# hx711.net
KiCad netlist of a schematic drawn in Altium Designer
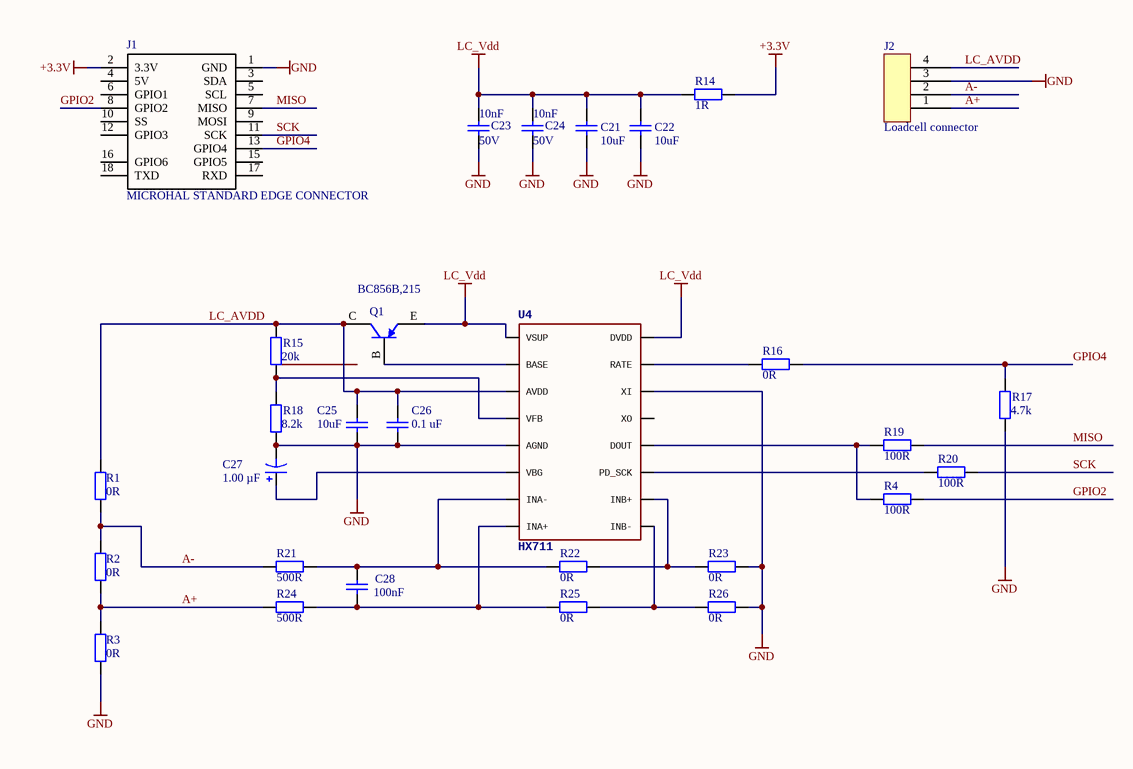
[diagram p0: hx711.SchDoc]

(export (version "E")
  (design (tool "Eeschema 10.0.6"))
  (components
    (comp (ref "C21")
      (value "AVX Interconnect / Elco TAJR106K006RNJ")
      (footprint "CAPC2113X120X50LL20T30")
      (description "CAP TANT 10UF 6.3V 10% 0805")
      (fields
        (field (name "VOLTAGE") "6.3VDC")
        (field (name "MANUFACTURER PART NUMBER") "TAJR106K006RNJ")
        (field (name "CAPACITANCE") "10uF")
      )
      (libsource (lib "CommunityVault") (part "CAP-2"))
    )
    (comp (ref "C22")
      (value "AVX Interconnect / Elco TAJR106K006RNJ")
      (footprint "CAPC2113X120X50LL20T30")
      (description "CAP TANT 10UF 6.3V 10% 0805")
      (fields
        (field (name "VOLTAGE") "6.3VDC")
        (field (name "MANUFACTURER PART NUMBER") "TAJR106K006RNJ")
        (field (name "CAPACITANCE") "10uF")
      )
      (libsource (lib "CommunityVault") (part "CAP-2"))
    )
    (comp (ref "C23")
      (value "0603N103J500")
      (footprint "PCB-19299713-1")
      (fields (field (name "CAPACITANCE") "10nF") (field (name "VOLTAGE RATING (DC)") "50V"))
      (libsource (lib "CommunityVault") (part "CMP-19299713-2"))
    )
    (comp (ref "C24")
      (value "0603N103J500")
      (footprint "PCB-19299713-1")
      (fields (field (name "CAPACITANCE") "10nF") (field (name "VOLTAGE RATING (DC)") "50V"))
      (libsource (lib "CommunityVault") (part "CMP-19299713-2"))
    )
    (comp (ref "C25")
      (value "AVX Interconnect / Elco TAJR106K006RNJ")
      (footprint "CAPC2113X120X50LL20T30")
      (description "CAP TANT 10UF 6.3V 10% 0805")
      (fields
        (field (name "VOLTAGE") "6.3VDC")
        (field (name "MANUFACTURER PART NUMBER") "TAJR106K006RNJ")
        (field (name "CAPACITANCE") "10uF")
      )
      (libsource (lib "CommunityVault") (part "CAP-2"))
    )
    (comp (ref "C26")
      (value "Murata GRM31C5C1E104JA01L")
      (footprint "PCB-121845-2")
      (description "CAP CER 0.1UF 25V 5% NP0 1206")
      (fields
        (field (name "TOLERANCE") "5 %")
        (field (name "MANUFACTURER") "Murata")
        (field (name "CAPACITANCE") "0.1 uF")
      )
      (libsource (lib "CommunityVault") (part "CMP-121845-1"))
    )
    (comp (ref "C27")
      (value "Kemet T491A105M016AT")
      (footprint "CAPC3216X180X80NL20T30")
      (description "Cap Tant Solid 1uF 16V A CASE 20% (3.2 X 1.6 X 1.6mm) SMD 3216-18 10 Ohm 125C Automotive T/R")
      (fields
        (field (name "MANUFACTURER PART NUMBER") "T491A105M016AT")
        (field (name "CAPACITANCE") "1.00 µF")
      )
      (libsource (lib "CommunityVault") (part "CMP-52579b5e2d498d90-1"))
    )
    (comp (ref "C28")
      (value "100nF")
      (footprint "PCB-121845-2")
      (description "CAP CER 0.1UF 25V 5% NP0 1206")
      (libsource (lib "CommunityVault") (part "CMP-121845-2"))
    )
    (comp (ref "J1")
      (value "MICROHAL STANDARD EDGE CONNECTOR")
      (footprint "PCB-n61ghpg3sznbl2uw6fwj-1")
      (description "microhal standard edge connector with 17 pins")
      (libsource (lib "CommunityVault") (part "CMP-6a3uyflm72uf0am1b36s-2"))
    )
    (comp (ref "J2")
      (value "Loadcell connector")
      (footprint "PCBComponent_1")
      (description "Wire-To-Board Connector, AMPMODU Mod II Series, Through Hole, Header, 4, 2.54 mm")
      (fields (field (name "MANUFACTURER PART NUMBER") "826926-4"))
      (libsource (lib "CommunityVault") (part "CMP-5c1097d27ab083d7-2"))
    )
    (comp (ref "Q1")
      (value "BC856B,215")
      (footprint "SOT23-BEC")
      (description "TRANS PNP 65V 0.1A SOT23")
      (libsource (lib "CommunityVault") (part "NXP-PNP-3"))
    )
    (comp (ref "R1")
      (value "~")
      (footprint "0603")
      (fields (field (name "RESISTANCE") "0R"))
      (libsource (lib "") (part "CMP-8f45450282185082-2_1"))
    )
    (comp (ref "R2")
      (value "~")
      (footprint "0603")
      (fields (field (name "RESISTANCE") "0R"))
      (libsource (lib "") (part "CMP-8f45450282185082-2_1"))
    )
    (comp (ref "R3")
      (value "~")
      (footprint "0603")
      (fields (field (name "RESISTANCE") "0R"))
      (libsource (lib "") (part "CMP-8f45450282185082-2_1"))
    )
    (comp (ref "R4")
      (value "~")
      (footprint "0603")
      (fields (field (name "RESISTANCE") "100R"))
      (libsource (lib "CommunityVault") (part "CMP-8f45450282185082-2"))
    )
    (comp (ref "R14")
      (value "~")
      (footprint "0603")
      (fields (field (name "RESISTANCE") "1R"))
      (libsource (lib "CommunityVault") (part "CMP-8f45450282185082-2"))
    )
    (comp (ref "R15")
      (value "~")
      (footprint "0603")
      (fields (field (name "RESISTANCE") "20k"))
      (libsource (lib "") (part "CMP-8f45450282185082-2_2"))
    )
    (comp (ref "R16")
      (value "~")
      (footprint "0603")
      (fields (field (name "RESISTANCE") "0R"))
      (libsource (lib "CommunityVault") (part "CMP-8f45450282185082-2"))
    )
    (comp (ref "R17")
      (value "~")
      (footprint "0603")
      (fields (field (name "RESISTANCE") "4.7k"))
      (libsource (lib "") (part "CMP-8f45450282185082-2_2"))
    )
    (comp (ref "R18")
      (value "~")
      (footprint "0603")
      (fields (field (name "RESISTANCE") "8.2k"))
      (libsource (lib "") (part "CMP-8f45450282185082-2_2"))
    )
    (comp (ref "R19")
      (value "~")
      (footprint "0603")
      (fields (field (name "RESISTANCE") "100R"))
      (libsource (lib "CommunityVault") (part "CMP-8f45450282185082-2"))
    )
    (comp (ref "R20")
      (value "~")
      (footprint "0603")
      (fields (field (name "RESISTANCE") "100R"))
      (libsource (lib "CommunityVault") (part "CMP-8f45450282185082-2"))
    )
    (comp (ref "R21")
      (value "~")
      (footprint "0603")
      (fields (field (name "RESISTANCE") "500R"))
      (libsource (lib "CommunityVault") (part "CMP-8f45450282185082-2"))
    )
    (comp (ref "R22")
      (value "~")
      (footprint "0603")
      (fields (field (name "RESISTANCE") "0R"))
      (libsource (lib "CommunityVault") (part "CMP-8f45450282185082-2"))
    )
    (comp (ref "R23")
      (value "~")
      (footprint "0603")
      (fields (field (name "RESISTANCE") "0R"))
      (libsource (lib "CommunityVault") (part "CMP-8f45450282185082-2"))
    )
    (comp (ref "R24")
      (value "~")
      (footprint "0603")
      (fields (field (name "RESISTANCE") "500R"))
      (libsource (lib "CommunityVault") (part "CMP-8f45450282185082-2"))
    )
    (comp (ref "R25")
      (value "~")
      (footprint "0603")
      (fields (field (name "RESISTANCE") "0R"))
      (libsource (lib "CommunityVault") (part "CMP-8f45450282185082-2"))
    )
    (comp (ref "R26")
      (value "~")
      (footprint "0603")
      (fields (field (name "RESISTANCE") "0R"))
      (libsource (lib "CommunityVault") (part "CMP-8f45450282185082-2"))
    )
    (comp (ref "U4")
      (value "HX711")
      (footprint "CYP-SX16_L")
      (description "Load Cell Amp HX711")
      (libsource (lib "CommunityVault") (part "SYM-8eb44445be3e5173-2"))
    )
  )
  (nets
    (net (code "1") (name "+3.3V") (class "Default")
      (node (ref "J1") (pin "2") (pinfunction "3.3V_2") (pintype "passive"))
      (node (ref "R14") (pin "1") (pinfunction "1_1") (pintype "passive"))
    )
    (net (code "2") (name "/A+") (class "Default")
      (node (ref "J2") (pin "1") (pinfunction "1_1") (pintype "passive"))
      (node (ref "R2") (pin "2") (pinfunction "2_2") (pintype "passive"))
      (node (ref "R24") (pin "2") (pinfunction "2_2") (pintype "passive"))
      (node (ref "R3") (pin "1") (pinfunction "1_1") (pintype "passive"))
    )
    (net (code "3") (name "/A-") (class "Default")
      (node (ref "J2") (pin "2") (pinfunction "2_2") (pintype "passive"))
      (node (ref "R1") (pin "2") (pinfunction "2_2") (pintype "passive"))
      (node (ref "R2") (pin "1") (pinfunction "1_1") (pintype "passive"))
      (node (ref "R21") (pin "2") (pinfunction "2_2") (pintype "passive"))
    )
    (net (code "4") (name "/GPIO2") (class "Default")
      (node (ref "J1") (pin "8") (pinfunction "GPIO2_8") (pintype "passive"))
      (node (ref "R4") (pin "1") (pinfunction "1_1") (pintype "passive"))
    )
    (net (code "5") (name "/GPIO4") (class "Default")
      (node (ref "J1") (pin "13") (pinfunction "GPIO4_13") (pintype "passive"))
      (node (ref "R16") (pin "1") (pinfunction "1_1") (pintype "passive"))
      (node (ref "R17") (pin "2") (pinfunction "2_2") (pintype "passive"))
    )
    (net (code "6") (name "/LC_AVDD") (class "Default")
      (node (ref "C25") (pin "2") (pinfunction "2_2") (pintype "passive"))
      (node (ref "C26") (pin "2") (pinfunction "2_2") (pintype "passive"))
      (node (ref "J2") (pin "4") (pinfunction "4_4") (pintype "passive"))
      (node (ref "Q1") (pin "C") (pinfunction "C_C") (pintype "passive"))
      (node (ref "R1") (pin "1") (pinfunction "1_1") (pintype "passive"))
      (node (ref "R15") (pin "2") (pinfunction "2_2") (pintype "passive"))
      (node (ref "U4") (pin "3") (pinfunction "AVDD_3") (pintype "passive"))
    )
    (net (code "7") (name "/MISO") (class "Default")
      (node (ref "J1") (pin "7") (pinfunction "MISO_7") (pintype "passive"))
      (node (ref "R19") (pin "1") (pinfunction "1_1") (pintype "passive"))
    )
    (net (code "8") (name "/SCK") (class "Default")
      (node (ref "J1") (pin "11") (pinfunction "SCK_11") (pintype "passive"))
      (node (ref "R20") (pin "1") (pinfunction "1_1") (pintype "passive"))
    )
    (net (code "9") (name "GND") (class "Default")
      (node (ref "C21") (pin "2") (pinfunction "2_2") (pintype "passive"))
      (node (ref "C22") (pin "2") (pinfunction "2_2") (pintype "passive"))
      (node (ref "C23") (pin "1") (pinfunction "1_1") (pintype "passive"))
      (node (ref "C24") (pin "1") (pinfunction "1_1") (pintype "passive"))
      (node (ref "C25") (pin "1") (pinfunction "1_1") (pintype "passive"))
      (node (ref "C26") (pin "1") (pinfunction "1_1") (pintype "passive"))
      (node (ref "C27") (pin "2") (pinfunction "-_2") (pintype "passive"))
      (node (ref "J1") (pin "1") (pinfunction "GND_1") (pintype "passive"))
      (node (ref "J2") (pin "3") (pinfunction "3_3") (pintype "passive"))
      (node (ref "R17") (pin "1") (pinfunction "1_1") (pintype "passive"))
      (node (ref "R18") (pin "1") (pinfunction "1_1") (pintype "passive"))
      (node (ref "R23") (pin "1") (pinfunction "1_1") (pintype "passive"))
      (node (ref "R26") (pin "1") (pinfunction "1_1") (pintype "passive"))
      (node (ref "R3") (pin "2") (pinfunction "2_2") (pintype "passive"))
      (node (ref "U4") (pin "14") (pinfunction "XI_14") (pintype "passive"))
      (node (ref "U4") (pin "5") (pinfunction "AGND_5") (pintype "passive"))
    )
    (net (code "10") (name "LC_Vdd") (class "Default")
      (node (ref "C21") (pin "1") (pinfunction "1_1") (pintype "passive"))
      (node (ref "C22") (pin "1") (pinfunction "1_1") (pintype "passive"))
      (node (ref "C23") (pin "2") (pinfunction "2_2") (pintype "passive"))
      (node (ref "C24") (pin "2") (pinfunction "2_2") (pintype "passive"))
      (node (ref "Q1") (pin "E") (pinfunction "E_E") (pintype "passive"))
      (node (ref "R14") (pin "2") (pinfunction "2_2") (pintype "passive"))
      (node (ref "U4") (pin "1") (pinfunction "VSUP_1") (pintype "passive"))
      (node (ref "U4") (pin "16") (pinfunction "DVDD_16") (pintype "passive"))
    )
    (net (code "11") (name "Net-(C27-+)") (class "Default")
      (node (ref "C27") (pin "1") (pinfunction "+_1") (pintype "passive"))
      (node (ref "U4") (pin "6") (pinfunction "VBG_6") (pintype "passive"))
    )
    (net (code "12") (name "Net-(U4-BASE)") (class "Default")
      (node (ref "Q1") (pin "B") (pinfunction "B_B") (pintype "passive"))
      (node (ref "U4") (pin "2") (pinfunction "BASE_2") (pintype "passive"))
    )
    (net (code "13") (name "Net-(U4-DOUT)") (class "Default")
      (node (ref "R19") (pin "2") (pinfunction "2_2") (pintype "passive"))
      (node (ref "R4") (pin "2") (pinfunction "2_2") (pintype "passive"))
      (node (ref "U4") (pin "12") (pinfunction "DOUT_12") (pintype "passive"))
    )
    (net (code "14") (name "Net-(U4-INA+)") (class "Default")
      (node (ref "C28") (pin "1") (pinfunction "1_1") (pintype "passive"))
      (node (ref "R24") (pin "1") (pinfunction "1_1") (pintype "passive"))
      (node (ref "R25") (pin "2") (pinfunction "2_2") (pintype "passive"))
      (node (ref "U4") (pin "8") (pinfunction "INA+_8") (pintype "passive"))
    )
    (net (code "15") (name "Net-(U4-INA-)") (class "Default")
      (node (ref "C28") (pin "2") (pinfunction "2_2") (pintype "passive"))
      (node (ref "R21") (pin "1") (pinfunction "1_1") (pintype "passive"))
      (node (ref "R22") (pin "2") (pinfunction "2_2") (pintype "passive"))
      (node (ref "U4") (pin "7") (pinfunction "INA-_7") (pintype "passive"))
    )
    (net (code "16") (name "Net-(U4-INB+)") (class "Default")
      (node (ref "R22") (pin "1") (pinfunction "1_1") (pintype "passive"))
      (node (ref "R23") (pin "2") (pinfunction "2_2") (pintype "passive"))
      (node (ref "U4") (pin "10") (pinfunction "INB+_10") (pintype "passive"))
    )
    (net (code "17") (name "Net-(U4-INB-)") (class "Default")
      (node (ref "R25") (pin "1") (pinfunction "1_1") (pintype "passive"))
      (node (ref "R26") (pin "2") (pinfunction "2_2") (pintype "passive"))
      (node (ref "U4") (pin "9") (pinfunction "INB-_9") (pintype "passive"))
    )
    (net (code "18") (name "Net-(U4-PD_SCK)") (class "Default")
      (node (ref "R20") (pin "2") (pinfunction "2_2") (pintype "passive"))
      (node (ref "U4") (pin "11") (pinfunction "PD_SCK_11") (pintype "passive"))
    )
    (net (code "19") (name "Net-(U4-RATE)") (class "Default")
      (node (ref "R16") (pin "2") (pinfunction "2_2") (pintype "passive"))
      (node (ref "U4") (pin "15") (pinfunction "RATE_15") (pintype "passive"))
    )
    (net (code "20") (name "Net-(U4-VFB)") (class "Default")
      (node (ref "R15") (pin "1") (pinfunction "1_1") (pintype "passive"))
      (node (ref "R18") (pin "2") (pinfunction "2_2") (pintype "passive"))
      (node (ref "U4") (pin "4") (pinfunction "VFB_4") (pintype "passive"))
    )
    (net (code "21") (name "unconnected-(J1-5V-Pad4)") (class "Default")
      (node (ref "J1") (pin "4") (pinfunction "5V_4") (pintype "passive"))
    )
    (net (code "22") (name "unconnected-(J1-GPIO1-Pad6)") (class "Default")
      (node (ref "J1") (pin "6") (pinfunction "GPIO1_6") (pintype "passive"))
    )
    (net (code "23") (name "unconnected-(J1-GPIO3-Pad12)") (class "Default")
      (node (ref "J1") (pin "12") (pinfunction "GPIO3_12") (pintype "passive"))
    )
    (net (code "24") (name "unconnected-(J1-GPIO5-Pad15)") (class "Default")
      (node (ref "J1") (pin "15") (pinfunction "GPIO5_15") (pintype "passive"))
    )
    (net (code "25") (name "unconnected-(J1-GPIO6-Pad16)") (class "Default")
      (node (ref "J1") (pin "16") (pinfunction "GPIO6_16") (pintype "passive"))
    )
    (net (code "26") (name "unconnected-(J1-MOSI-Pad9)") (class "Default")
      (node (ref "J1") (pin "9") (pinfunction "MOSI_9") (pintype "passive"))
    )
    (net (code "27") (name "unconnected-(J1-RXD-Pad17)") (class "Default")
      (node (ref "J1") (pin "17") (pinfunction "RXD_17") (pintype "passive"))
    )
    (net (code "28") (name "unconnected-(J1-SCL-Pad5)") (class "Default")
      (node (ref "J1") (pin "5") (pinfunction "SCL_5") (pintype "passive"))
    )
    (net (code "29") (name "unconnected-(J1-SDA-Pad3)") (class "Default")
      (node (ref "J1") (pin "3") (pinfunction "SDA_3") (pintype "passive"))
    )
    (net (code "30") (name "unconnected-(J1-SS-Pad10)") (class "Default")
      (node (ref "J1") (pin "10") (pinfunction "SS_10") (pintype "passive"))
    )
    (net (code "31") (name "unconnected-(J1-TXD-Pad18)") (class "Default")
      (node (ref "J1") (pin "18") (pinfunction "TXD_18") (pintype "passive"))
    )
    (net (code "32") (name "unconnected-(U4-XO-Pad13)") (class "Default")
      (node (ref "U4") (pin "13") (pinfunction "XO_13") (pintype "passive"))
    )
  )
)
